# DOCKING_IR-BUMPER-SENSOR.net
KiCad netlist of a schematic drawn in Altium Designer
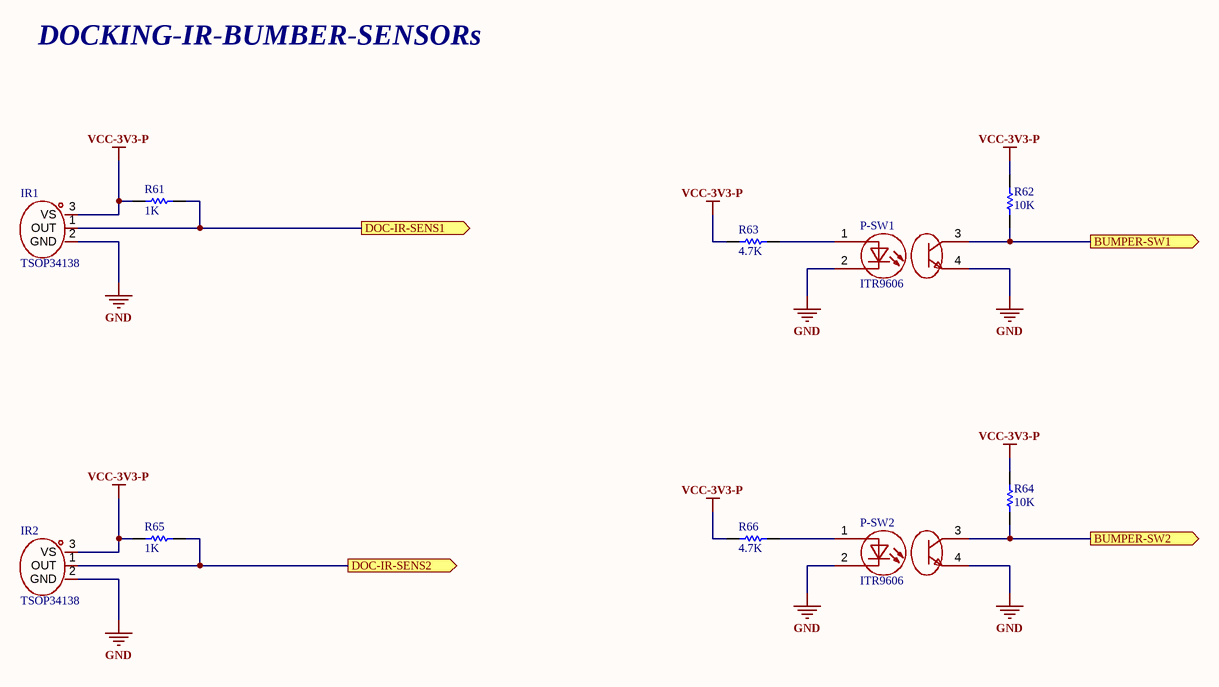
[diagram p0: DOCKING IR-BUMPER-SENSOR.SchDoc]

(export (version "E")
  (design (tool "Eeschema 10.0.6"))
  (components
    (comp (ref "IR1")
      (value "TSOP34138")
      (footprint "SENSOR-TH_TSOP32138")
      (libsource (lib "DesignLibrary") (part "IR-RECEIVER"))
    )
    (comp (ref "IR2")
      (value "TSOP34138")
      (footprint "SENSOR-TH_TSOP32138")
      (libsource (lib "DesignLibrary") (part "IR-RECEIVER"))
    )
    (comp (ref "P-SW1")
      (value "ITR9606")
      (footprint "OPTO-TH_4P_ITR9606")
      (libsource (lib "DesignLibrary") (part "OPTO-IR-SW"))
    )
    (comp (ref "P-SW2")
      (value "ITR9606")
      (footprint "OPTO-TH_4P_ITR9606")
      (libsource (lib "DesignLibrary") (part "OPTO-IR-SW"))
    )
    (comp (ref "R61")
      (value "1K")
      (footprint "RES-0402")
      (libsource (lib "DesignLibrary") (part "Resistor-1"))
    )
    (comp (ref "R62")
      (value "10K")
      (footprint "RES-0402")
      (libsource (lib "DesignLibrary") (part "Resistor-1"))
    )
    (comp (ref "R63")
      (value "4.7K")
      (footprint "RES-0402")
      (libsource (lib "DesignLibrary") (part "Resistor-1"))
    )
    (comp (ref "R64")
      (value "10K")
      (footprint "RES-0402")
      (libsource (lib "DesignLibrary") (part "Resistor-1"))
    )
    (comp (ref "R65")
      (value "1K")
      (footprint "RES-0402")
      (libsource (lib "DesignLibrary") (part "Resistor-1"))
    )
    (comp (ref "R66")
      (value "4.7K")
      (footprint "RES-0402")
      (libsource (lib "DesignLibrary") (part "Resistor-1"))
    )
  )
  (nets
    (net (code "1") (name "/BUMPER-SW1") (class "Default")
      (node (ref "P-SW1") (pin "3") (pinfunction "3_3") (pintype "passive"))
      (node (ref "R62") (pin "1") (pintype "passive"))
    )
    (net (code "2") (name "/BUMPER-SW2") (class "Default")
      (node (ref "P-SW2") (pin "3") (pinfunction "3_3") (pintype "passive"))
      (node (ref "R64") (pin "1") (pintype "passive"))
    )
    (net (code "3") (name "/DOC-IR-SENS1") (class "Default")
      (node (ref "IR1") (pin "1") (pinfunction "OUT_1") (pintype "passive"))
      (node (ref "R61") (pin "1") (pintype "passive"))
    )
    (net (code "4") (name "/DOC-IR-SENS2") (class "Default")
      (node (ref "IR2") (pin "1") (pinfunction "OUT_1") (pintype "passive"))
      (node (ref "R65") (pin "1") (pintype "passive"))
    )
    (net (code "5") (name "GND") (class "Default")
      (node (ref "IR1") (pin "2") (pinfunction "GND_2") (pintype "passive"))
      (node (ref "IR2") (pin "2") (pinfunction "GND_2") (pintype "passive"))
      (node (ref "P-SW1") (pin "2") (pinfunction "2_2") (pintype "passive"))
      (node (ref "P-SW1") (pin "4") (pinfunction "4_4") (pintype "passive"))
      (node (ref "P-SW2") (pin "2") (pinfunction "2_2") (pintype "passive"))
      (node (ref "P-SW2") (pin "4") (pinfunction "4_4") (pintype "passive"))
    )
    (net (code "6") (name "Net-(P-SW1-Pad1)") (class "Default")
      (node (ref "P-SW1") (pin "1") (pinfunction "1_1") (pintype "passive"))
      (node (ref "R63") (pin "1") (pintype "passive"))
    )
    (net (code "7") (name "Net-(P-SW2-Pad1)") (class "Default")
      (node (ref "P-SW2") (pin "1") (pinfunction "1_1") (pintype "passive"))
      (node (ref "R66") (pin "1") (pintype "passive"))
    )
    (net (code "8") (name "VCC-3V3-P") (class "Default")
      (node (ref "IR1") (pin "3") (pinfunction "VS_3") (pintype "passive"))
      (node (ref "IR2") (pin "3") (pinfunction "VS_3") (pintype "passive"))
      (node (ref "R61") (pin "2") (pintype "passive"))
      (node (ref "R62") (pin "2") (pintype "passive"))
      (node (ref "R63") (pin "2") (pintype "passive"))
      (node (ref "R64") (pin "2") (pintype "passive"))
      (node (ref "R65") (pin "2") (pintype "passive"))
      (node (ref "R66") (pin "2") (pintype "passive"))
    )
  )
)
